# SCH___2021-11-10.net
KiCad netlist of a schematic drawn in EasyEDA
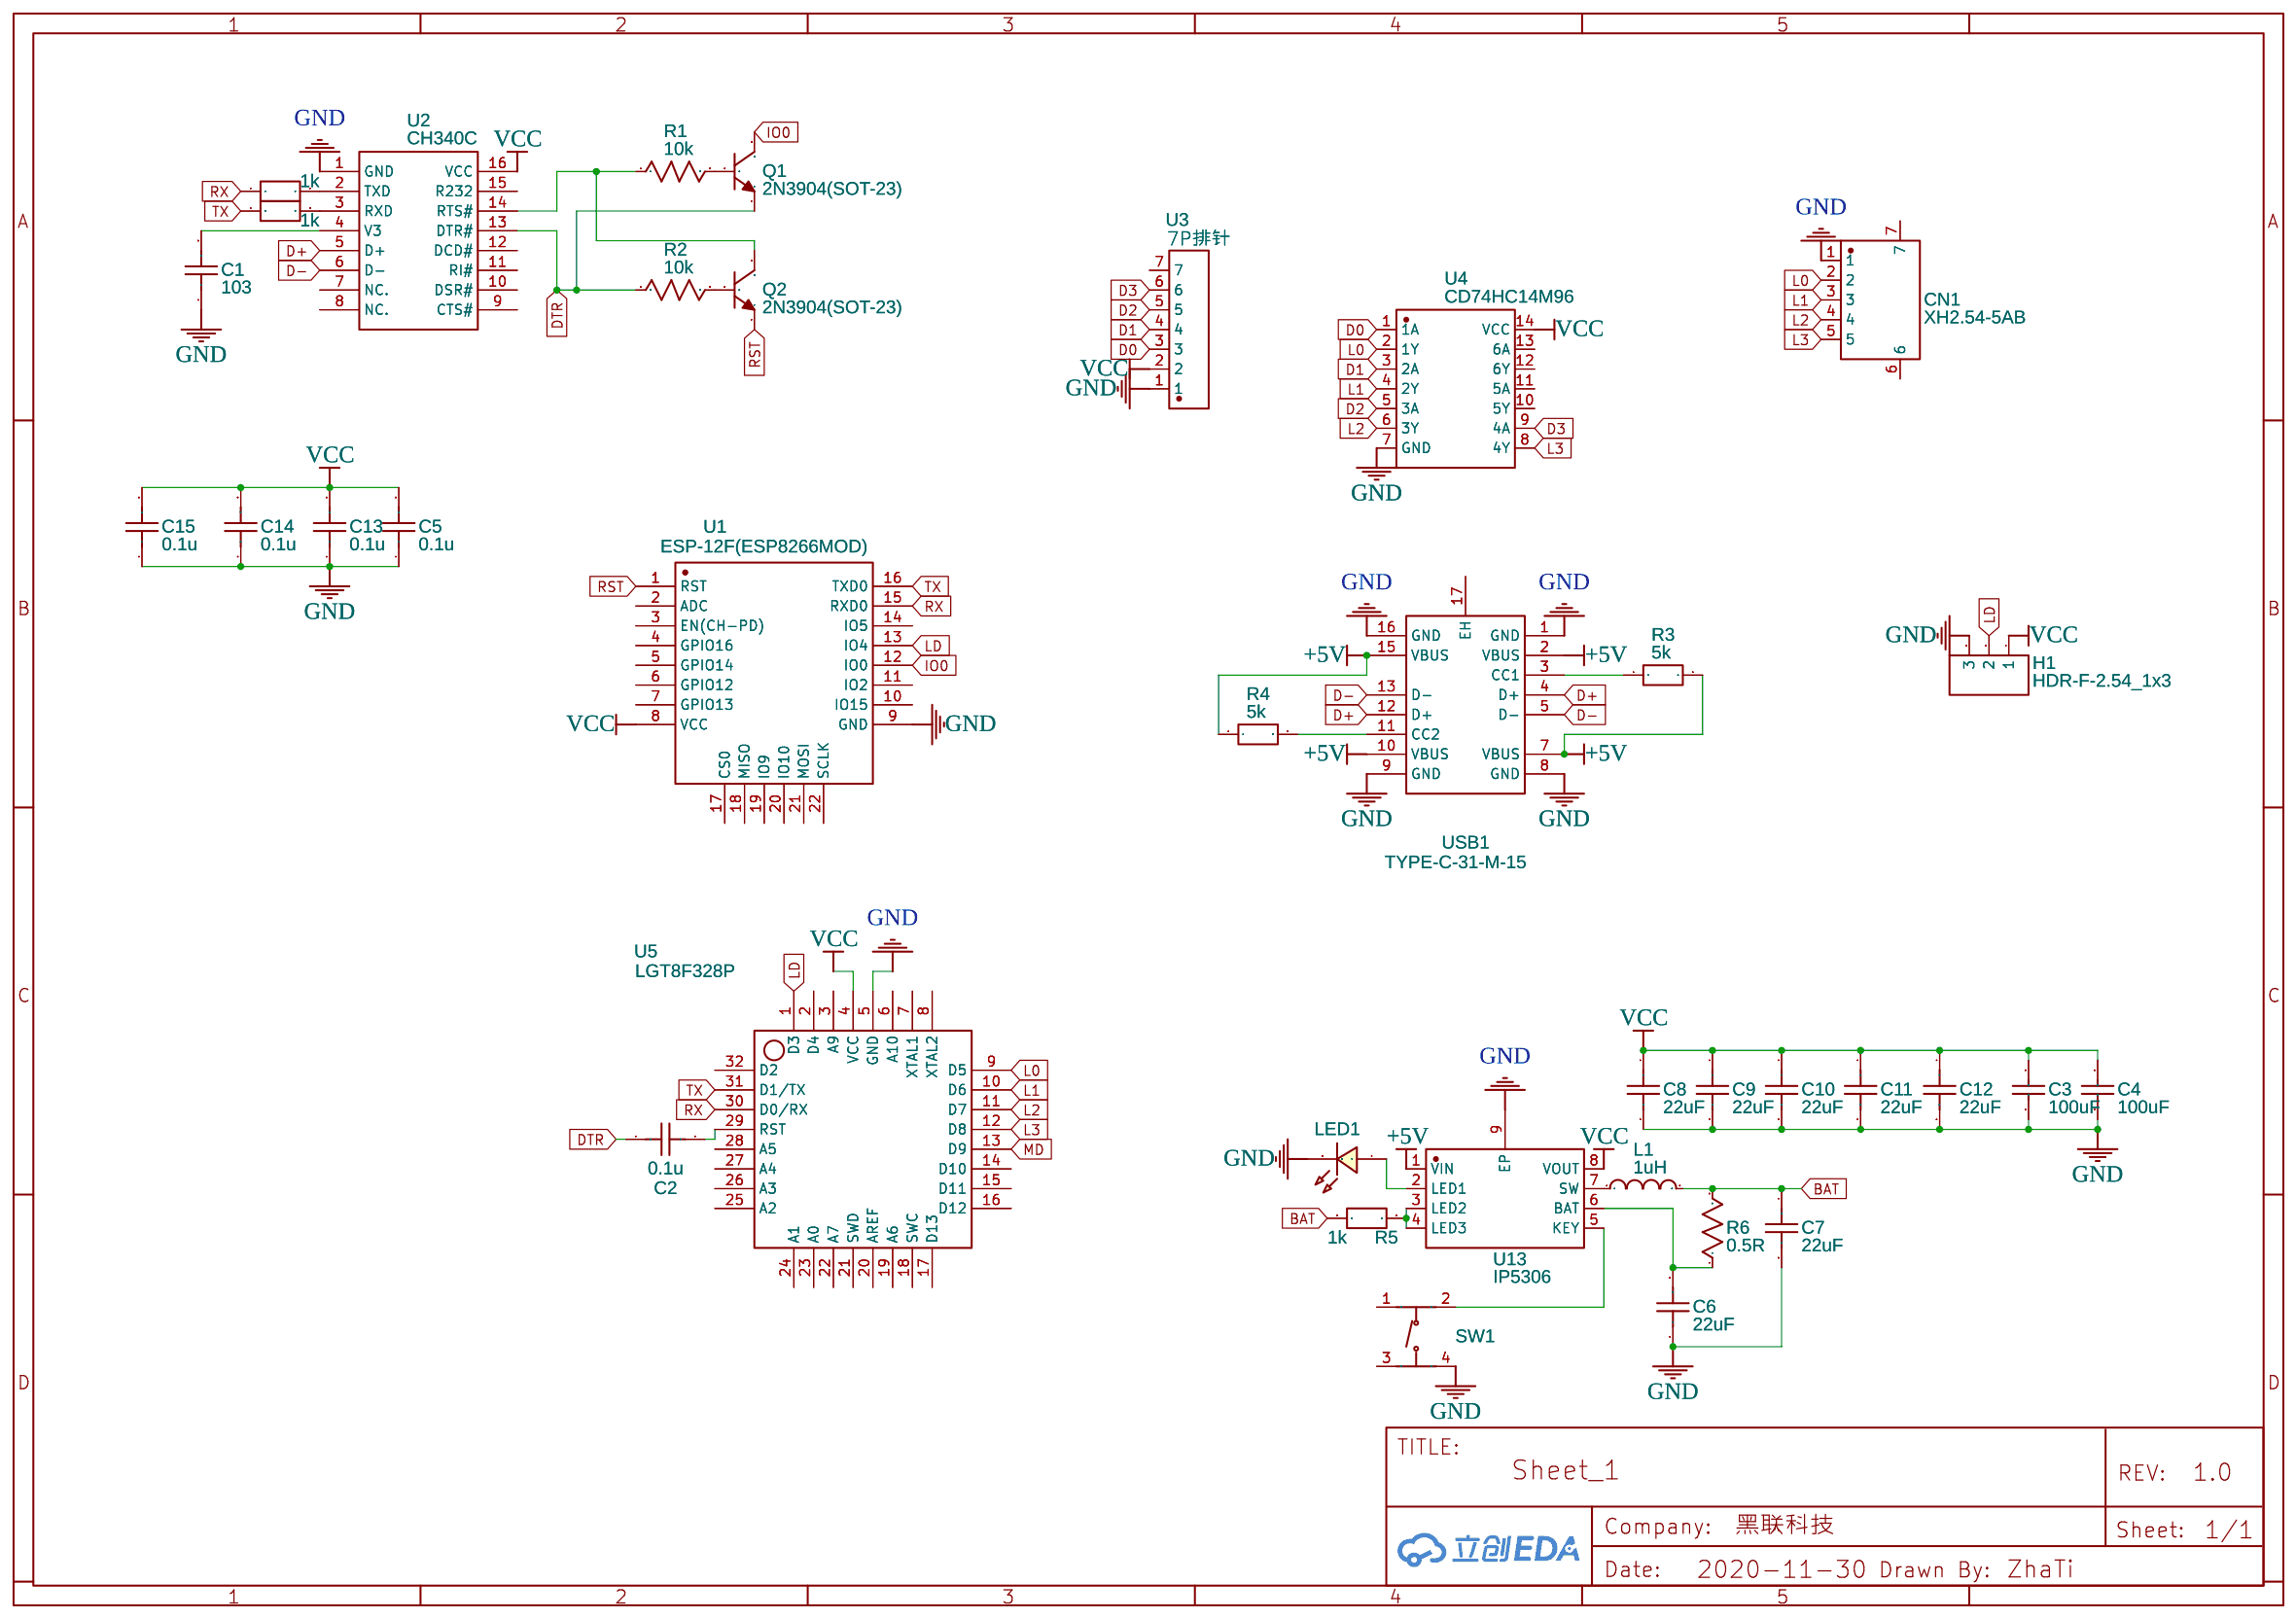
[diagram p0: schematic sheet]

(export (version "E")
  (design (tool "Eeschema 10.0.6"))
  (components
    (comp (ref "C1") (value "103") (libsource (lib "") (part "C_0603_US")))
    (comp (ref "C2") (value "0.1u") (libsource (lib "") (part "C_0603_US_1")))
    (comp (ref "C3")
      (value "100uF")
      (fields
        (field (name "BOM_Manufacturer Part") "1210B472K251NT")
        (field (name "BOM_Supplier Part") "C52019")
      )
      (libsource (lib "") (part "1210B472K251NT"))
    )
    (comp (ref "C4")
      (value "100uF")
      (fields
        (field (name "BOM_Manufacturer Part") "1210B472K251NT")
        (field (name "BOM_Supplier Part") "C52019")
      )
      (libsource (lib "") (part "1210B472K251NT"))
    )
    (comp (ref "C5") (value "0.1u") (libsource (lib "") (part "C_0603_US")))
    (comp (ref "C6")
      (value "22uF")
      (fields
        (field (name "BOM_Manufacturer Part") "CL21A226MQQNNNE")
        (field (name "BOM_Supplier Part") "C5674")
      )
      (libsource (lib "") (part "CL21A226MQQNNNE_1"))
    )
    (comp (ref "C7")
      (value "22uF")
      (fields
        (field (name "BOM_Manufacturer Part") "CL21A226MQQNNNE")
        (field (name "BOM_Supplier Part") "C5674")
      )
      (libsource (lib "") (part "CL21A226MQQNNNE"))
    )
    (comp (ref "C8")
      (value "22uF")
      (fields
        (field (name "BOM_Manufacturer Part") "CL21A226MQQNNNE")
        (field (name "BOM_Supplier Part") "C5674")
      )
      (libsource (lib "") (part "CL21A226MQQNNNE"))
    )
    (comp (ref "C9")
      (value "22uF")
      (fields
        (field (name "BOM_Manufacturer Part") "CL21A226MQQNNNE")
        (field (name "BOM_Supplier Part") "C5674")
      )
      (libsource (lib "") (part "CL21A226MQQNNNE"))
    )
    (comp (ref "C10")
      (value "22uF")
      (fields
        (field (name "BOM_Manufacturer Part") "CL21A226MQQNNNE")
        (field (name "BOM_Supplier Part") "C5674")
      )
      (libsource (lib "") (part "CL21A226MQQNNNE"))
    )
    (comp (ref "C11")
      (value "22uF")
      (fields
        (field (name "BOM_Manufacturer Part") "CL21A226MQQNNNE")
        (field (name "BOM_Supplier Part") "C5674")
      )
      (libsource (lib "") (part "CL21A226MQQNNNE"))
    )
    (comp (ref "C12")
      (value "22uF")
      (fields
        (field (name "BOM_Manufacturer Part") "CL21A226MQQNNNE")
        (field (name "BOM_Supplier Part") "C5674")
      )
      (libsource (lib "") (part "CL21A226MQQNNNE"))
    )
    (comp (ref "C13") (value "0.1u") (libsource (lib "") (part "C_0603_US")))
    (comp (ref "C14") (value "0.1u") (libsource (lib "") (part "C_0603_US")))
    (comp (ref "C15") (value "0.1u") (libsource (lib "") (part "C_0603_US")))
    (comp (ref "CN1")
      (value "XH2.54-5AB")
      (fields (field (name "BOM_Supplier Part") "C146128"))
      (libsource (lib "") (part "XH2.54-5AB"))
    )
    (comp (ref "H1")
      (value "HDR-F-2.54_1x3")
      (fields (field (name "BOM_Supplier Part") "C146690"))
      (libsource (lib "") (part "HDR-F-2.54_1x3"))
    )
    (comp (ref "L1")
      (value "1uH")
      (fields
        (field (name "BOM_Manufacturer Part") "SPM6530T-1R0M120")
        (field (name "BOM_Supplier Part") "C87572")
      )
      (libsource (lib "") (part "SPM6530T-1R0M120"))
    )
    (comp (ref "LED1")
      (value "LED-0603_R")
      (fields
        (field (name "BOM_Manufacturer Part") "19-217/R6C-AL1M2VY/3T")
        (field (name "BOM_Supplier Part") "C72044")
      )
      (libsource (lib "") (part "LED-0603_R"))
    )
    (comp (ref "Q1")
      (value "2N3904(SOT-23)")
      (fields
        (field (name "BOM_Manufacturer Part") "2n3904S-RTK/PS")
        (field (name "BOM_Supplier Part") "C18536")
      )
      (libsource (lib "") (part "2N3904(SOT-23)"))
    )
    (comp (ref "Q2")
      (value "2N3904(SOT-23)")
      (fields
        (field (name "BOM_Manufacturer Part") "2n3904S-RTK/PS")
        (field (name "BOM_Supplier Part") "C18536")
      )
      (libsource (lib "") (part "2N3904(SOT-23)"))
    )
    (comp (ref "R1") (value "10k") (libsource (lib "") (part "R_0603_US")))
    (comp (ref "R2") (value "10k") (libsource (lib "") (part "R_0603_US")))
    (comp (ref "R3") (value "5k") (libsource (lib "") (part "R_0603_EU")))
    (comp (ref "R4") (value "5k") (libsource (lib "") (part "R_0603_EU")))
    (comp (ref "R5") (value "1k") (libsource (lib "") (part "R_0603_EU")))
    (comp (ref "R6") (value "0.5R") (libsource (lib "") (part "R_0603_US_1")))
    (comp (ref "R7") (value "1k") (libsource (lib "") (part "R_0603_EU")))
    (comp (ref "R8") (value "1k") (libsource (lib "") (part "R_0603_EU")))
    (comp (ref "SW1")
      (value "TS-1187A-B-A-B")
      (fields (field (name "BOM_Supplier Part") "C318884"))
      (libsource (lib "") (part "TS-1187A-B-A-B"))
    )
    (comp (ref "U1")
      (value "ESP-12F(ESP8266MOD)")
      (fields (field (name "BOM_Supplier Part") "C82891"))
      (libsource (lib "") (part "ESP-12F(ESP8266MOD)"))
    )
    (comp (ref "U2")
      (value "CH340C")
      (fields (field (name "BOM_Supplier Part") "C84681"))
      (libsource (lib "") (part "CH340C"))
    )
    (comp (ref "U3") (value "7P排针") (libsource (lib "") (part "7P")))
    (comp (ref "U4")
      (value "CD74HC14M96")
      (fields (field (name "BOM_Supplier Part") "C74640"))
      (libsource (lib "") (part "CD74HC14M96"))
    )
    (comp (ref "U5") (value "LGT8F328P") (libsource (lib "") (part "LGT8F328P")))
    (comp (ref "U13")
      (value "IP5306")
      (fields (field (name "BOM_Supplier Part") "C181692"))
      (libsource (lib "") (part "IP5306"))
    )
    (comp (ref "USB1")
      (value "TYPE-C-31-M-15")
      (fields (field (name "BOM_Supplier Part") "C223908"))
      (libsource (lib "") (part "TYPE-C-31-M-15"))
    )
  )
  (nets
    (net (code "1") (name "+5V") (class "Default")
      (node (ref "R3") (pin "2") (pinfunction "2_2") (pintype "unspecified"))
      (node (ref "R4") (pin "1") (pinfunction "1_1") (pintype "unspecified"))
      (node (ref "U13") (pin "1") (pinfunction "VIN_1") (pintype "unspecified"))
      (node (ref "USB1") (pin "10") (pinfunction "VBUS_10") (pintype "unspecified"))
      (node (ref "USB1") (pin "15") (pinfunction "VBUS_15") (pintype "unspecified"))
      (node (ref "USB1") (pin "2") (pinfunction "VBUS_2") (pintype "unspecified"))
      (node (ref "USB1") (pin "7") (pinfunction "VBUS_7") (pintype "unspecified"))
    )
    (net (code "2") (name "BAT") (class "Default")
      (node (ref "C7") (pin "1") (pinfunction "1_1") (pintype "unspecified"))
      (node (ref "L1") (pin "2") (pinfunction "2_2") (pintype "unspecified"))
      (node (ref "R5") (pin "1") (pinfunction "1_1") (pintype "unspecified"))
      (node (ref "R6") (pin "2") (pinfunction "2_2") (pintype "unspecified"))
    )
    (net (code "3") (name "D+") (class "Default")
      (node (ref "U2") (pin "5") (pinfunction "D+_5") (pintype "unspecified"))
      (node (ref "USB1") (pin "12") (pinfunction "D+_12") (pintype "unspecified"))
      (node (ref "USB1") (pin "4") (pinfunction "D+_4") (pintype "unspecified"))
    )
    (net (code "4") (name "D-") (class "Default")
      (node (ref "U2") (pin "6") (pinfunction "D-_6") (pintype "unspecified"))
      (node (ref "USB1") (pin "13") (pinfunction "D-_13") (pintype "unspecified"))
      (node (ref "USB1") (pin "5") (pinfunction "D-_5") (pintype "unspecified"))
    )
    (net (code "5") (name "D0") (class "Default")
      (node (ref "U3") (pin "3") (pinfunction "3_3") (pintype "unspecified"))
      (node (ref "U4") (pin "1") (pinfunction "1A_1") (pintype "unspecified"))
    )
    (net (code "6") (name "D1") (class "Default")
      (node (ref "U3") (pin "4") (pinfunction "4_4") (pintype "unspecified"))
      (node (ref "U4") (pin "3") (pinfunction "2A_3") (pintype "unspecified"))
    )
    (net (code "7") (name "D2") (class "Default")
      (node (ref "U3") (pin "5") (pinfunction "5_5") (pintype "unspecified"))
      (node (ref "U4") (pin "5") (pinfunction "3A_5") (pintype "unspecified"))
    )
    (net (code "8") (name "D3") (class "Default")
      (node (ref "U3") (pin "6") (pinfunction "6_6") (pintype "unspecified"))
      (node (ref "U4") (pin "9") (pinfunction "4A_9") (pintype "unspecified"))
    )
    (net (code "9") (name "DTR") (class "Default")
      (node (ref "C2") (pin "1") (pinfunction "1_1") (pintype "unspecified"))
      (node (ref "Q1") (pin "1") (pinfunction "E_1") (pintype "input"))
      (node (ref "R2") (pin "1") (pinfunction "1_1") (pintype "unspecified"))
      (node (ref "U2") (pin "13") (pinfunction "DTR#_13") (pintype "unspecified"))
    )
    (net (code "10") (name "GND") (class "Default")
      (node (ref "C1") (pin "1") (pinfunction "1_1") (pintype "unspecified"))
      (node (ref "C10") (pin "2") (pinfunction "2_2") (pintype "unspecified"))
      (node (ref "C11") (pin "2") (pinfunction "2_2") (pintype "unspecified"))
      (node (ref "C12") (pin "2") (pinfunction "2_2") (pintype "unspecified"))
      (node (ref "C13") (pin "1") (pinfunction "1_1") (pintype "unspecified"))
      (node (ref "C14") (pin "1") (pinfunction "1_1") (pintype "unspecified"))
      (node (ref "C15") (pin "1") (pinfunction "1_1") (pintype "unspecified"))
      (node (ref "C3") (pin "1") (pinfunction "1_1") (pintype "input"))
      (node (ref "C4") (pin "1") (pinfunction "1_1") (pintype "input"))
      (node (ref "C5") (pin "1") (pinfunction "1_1") (pintype "unspecified"))
      (node (ref "C6") (pin "1") (pinfunction "1_1") (pintype "unspecified"))
      (node (ref "C7") (pin "2") (pinfunction "2_2") (pintype "unspecified"))
      (node (ref "C8") (pin "2") (pinfunction "2_2") (pintype "unspecified"))
      (node (ref "C9") (pin "2") (pinfunction "2_2") (pintype "unspecified"))
      (node (ref "CN1") (pin "1") (pinfunction "1_1") (pintype "unspecified"))
      (node (ref "H1") (pin "3") (pinfunction "3_3") (pintype "input"))
      (node (ref "LED1") (pin "2") (pinfunction "2_2") (pintype "unspecified"))
      (node (ref "SW1") (pin "4") (pinfunction "D_4") (pintype "unspecified"))
      (node (ref "U1") (pin "9") (pinfunction "GND_9") (pintype "unspecified"))
      (node (ref "U13") (pin "9") (pinfunction "EP_9") (pintype "unspecified"))
      (node (ref "U2") (pin "1") (pinfunction "GND_1") (pintype "unspecified"))
      (node (ref "U3") (pin "1") (pinfunction "1_1") (pintype "unspecified"))
      (node (ref "U4") (pin "7") (pinfunction "GND_7") (pintype "unspecified"))
      (node (ref "U5") (pin "5") (pinfunction "GND_5") (pintype "unspecified"))
      (node (ref "USB1") (pin "1") (pinfunction "GND_1") (pintype "unspecified"))
      (node (ref "USB1") (pin "16") (pinfunction "GND_16") (pintype "unspecified"))
      (node (ref "USB1") (pin "8") (pinfunction "GND_8") (pintype "unspecified"))
      (node (ref "USB1") (pin "9") (pinfunction "GND_9") (pintype "unspecified"))
    )
    (net (code "11") (name "IO0") (class "Default")
      (node (ref "Q1") (pin "3") (pinfunction "C_3") (pintype "input"))
      (node (ref "U1") (pin "12") (pinfunction "IO0_12") (pintype "unspecified"))
    )
    (net (code "12") (name "L0") (class "Default")
      (node (ref "CN1") (pin "2") (pinfunction "2_2") (pintype "unspecified"))
      (node (ref "U4") (pin "2") (pinfunction "1Y_2") (pintype "unspecified"))
      (node (ref "U5") (pin "9") (pinfunction "D5_9") (pintype "unspecified"))
    )
    (net (code "13") (name "L1") (class "Default")
      (node (ref "CN1") (pin "3") (pinfunction "3_3") (pintype "unspecified"))
      (node (ref "U4") (pin "4") (pinfunction "2Y_4") (pintype "unspecified"))
      (node (ref "U5") (pin "10") (pinfunction "D6_10") (pintype "unspecified"))
    )
    (net (code "14") (name "L2") (class "Default")
      (node (ref "CN1") (pin "4") (pinfunction "4_4") (pintype "unspecified"))
      (node (ref "U4") (pin "6") (pinfunction "3Y_6") (pintype "unspecified"))
      (node (ref "U5") (pin "11") (pinfunction "D7_11") (pintype "unspecified"))
    )
    (net (code "15") (name "L3") (class "Default")
      (node (ref "CN1") (pin "5") (pinfunction "5_5") (pintype "unspecified"))
      (node (ref "U4") (pin "8") (pinfunction "4Y_8") (pintype "unspecified"))
      (node (ref "U5") (pin "12") (pinfunction "D8_12") (pintype "unspecified"))
    )
    (net (code "16") (name "LD") (class "Default")
      (node (ref "H1") (pin "2") (pinfunction "2_2") (pintype "input"))
      (node (ref "U1") (pin "13") (pinfunction "IO4_13") (pintype "unspecified"))
      (node (ref "U5") (pin "1") (pinfunction "D3_1") (pintype "unspecified"))
    )
    (net (code "17") (name "MD") (class "Default")
      (node (ref "U5") (pin "13") (pinfunction "D9_13") (pintype "unspecified"))
    )
    (net (code "18") (name "Net-(Q1-B)") (class "Default")
      (node (ref "Q1") (pin "2") (pinfunction "B_2") (pintype "input"))
      (node (ref "R1") (pin "2") (pinfunction "2_2") (pintype "unspecified"))
    )
    (net (code "19") (name "Net-(Q2-B)") (class "Default")
      (node (ref "Q2") (pin "2") (pinfunction "B_2") (pintype "input"))
      (node (ref "R2") (pin "2") (pinfunction "2_2") (pintype "unspecified"))
    )
    (net (code "20") (name "Net-(Q2-C)") (class "Default")
      (node (ref "Q2") (pin "3") (pinfunction "C_3") (pintype "input"))
      (node (ref "R1") (pin "1") (pinfunction "1_1") (pintype "unspecified"))
      (node (ref "U2") (pin "14") (pinfunction "RTS#_14") (pintype "unspecified"))
    )
    (net (code "21") (name "Net-(SW1-B)") (class "Default")
      (node (ref "SW1") (pin "2") (pinfunction "B_2") (pintype "unspecified"))
      (node (ref "U13") (pin "5") (pinfunction "KEY_5") (pintype "unspecified"))
    )
    (net (code "22") (name "Net-(U2-RXD)") (class "Default")
      (node (ref "R8") (pin "2") (pinfunction "2_2") (pintype "unspecified"))
      (node (ref "U2") (pin "3") (pinfunction "RXD_3") (pintype "unspecified"))
    )
    (net (code "23") (name "Net-(U2-TXD)") (class "Default")
      (node (ref "R7") (pin "2") (pinfunction "2_2") (pintype "unspecified"))
      (node (ref "U2") (pin "2") (pinfunction "TXD_2") (pintype "unspecified"))
    )
    (net (code "24") (name "Net-(U2-V3)") (class "Default")
      (node (ref "C1") (pin "2") (pinfunction "2_2") (pintype "unspecified"))
      (node (ref "U2") (pin "4") (pinfunction "V3_4") (pintype "unspecified"))
    )
    (net (code "25") (name "Net-(U5-RST)") (class "Default")
      (node (ref "C2") (pin "2") (pinfunction "2_2") (pintype "unspecified"))
      (node (ref "U5") (pin "29") (pinfunction "RST_29") (pintype "unspecified"))
    )
    (net (code "26") (name "Net-(U13-BAT)") (class "Default")
      (node (ref "C6") (pin "2") (pinfunction "2_2") (pintype "unspecified"))
      (node (ref "R6") (pin "1") (pinfunction "1_1") (pintype "unspecified"))
      (node (ref "U13") (pin "6") (pinfunction "BAT_6") (pintype "unspecified"))
    )
    (net (code "27") (name "Net-(U13-LED1)") (class "Default")
      (node (ref "LED1") (pin "1") (pinfunction "1_1") (pintype "unspecified"))
      (node (ref "U13") (pin "2") (pinfunction "LED1_2") (pintype "unspecified"))
    )
    (net (code "28") (name "Net-(U13-LED2)") (class "Default")
      (node (ref "R5") (pin "2") (pinfunction "2_2") (pintype "unspecified"))
      (node (ref "U13") (pin "3") (pinfunction "LED2_3") (pintype "unspecified"))
      (node (ref "U13") (pin "4") (pinfunction "LED3_4") (pintype "unspecified"))
    )
    (net (code "29") (name "Net-(U13-SW)") (class "Default")
      (node (ref "L1") (pin "1") (pinfunction "1_1") (pintype "unspecified"))
      (node (ref "U13") (pin "7") (pinfunction "SW_7") (pintype "unspecified"))
    )
    (net (code "30") (name "Net-(USB1-CC1)") (class "Default")
      (node (ref "R3") (pin "1") (pinfunction "1_1") (pintype "unspecified"))
      (node (ref "USB1") (pin "3") (pinfunction "CC1_3") (pintype "unspecified"))
    )
    (net (code "31") (name "Net-(USB1-CC2)") (class "Default")
      (node (ref "R4") (pin "2") (pinfunction "2_2") (pintype "unspecified"))
      (node (ref "USB1") (pin "11") (pinfunction "CC2_11") (pintype "unspecified"))
    )
    (net (code "32") (name "RST") (class "Default")
      (node (ref "Q2") (pin "1") (pinfunction "E_1") (pintype "input"))
      (node (ref "U1") (pin "1") (pinfunction "RST_1") (pintype "unspecified"))
    )
    (net (code "33") (name "RX") (class "Default")
      (node (ref "R7") (pin "1") (pinfunction "1_1") (pintype "unspecified"))
      (node (ref "U1") (pin "15") (pinfunction "RXD0_15") (pintype "unspecified"))
      (node (ref "U5") (pin "30") (pinfunction "D0/RX_30") (pintype "unspecified"))
    )
    (net (code "34") (name "TX") (class "Default")
      (node (ref "R8") (pin "1") (pinfunction "1_1") (pintype "unspecified"))
      (node (ref "U1") (pin "16") (pinfunction "TXD0_16") (pintype "unspecified"))
      (node (ref "U5") (pin "31") (pinfunction "D1/TX_31") (pintype "unspecified"))
    )
    (net (code "35") (name "VCC") (class "Default")
      (node (ref "C10") (pin "1") (pinfunction "1_1") (pintype "unspecified"))
      (node (ref "C11") (pin "1") (pinfunction "1_1") (pintype "unspecified"))
      (node (ref "C12") (pin "1") (pinfunction "1_1") (pintype "unspecified"))
      (node (ref "C13") (pin "2") (pinfunction "2_2") (pintype "unspecified"))
      (node (ref "C14") (pin "2") (pinfunction "2_2") (pintype "unspecified"))
      (node (ref "C15") (pin "2") (pinfunction "2_2") (pintype "unspecified"))
      (node (ref "C3") (pin "2") (pinfunction "2_2") (pintype "input"))
      (node (ref "C4") (pin "2") (pinfunction "2_2") (pintype "input"))
      (node (ref "C5") (pin "2") (pinfunction "2_2") (pintype "unspecified"))
      (node (ref "C8") (pin "1") (pinfunction "1_1") (pintype "unspecified"))
      (node (ref "C9") (pin "1") (pinfunction "1_1") (pintype "unspecified"))
      (node (ref "H1") (pin "1") (pinfunction "1_1") (pintype "input"))
      (node (ref "U1") (pin "8") (pinfunction "VCC_8") (pintype "unspecified"))
      (node (ref "U13") (pin "8") (pinfunction "VOUT_8") (pintype "unspecified"))
      (node (ref "U2") (pin "16") (pinfunction "VCC_16") (pintype "unspecified"))
      (node (ref "U3") (pin "2") (pinfunction "2_2") (pintype "unspecified"))
      (node (ref "U4") (pin "14") (pinfunction "VCC_14") (pintype "unspecified"))
      (node (ref "U5") (pin "4") (pinfunction "VCC_4") (pintype "unspecified"))
    )
    (net (code "36") (name "unconnected-(CN1-Pad6)") (class "Default")
      (node (ref "CN1") (pin "6") (pinfunction "6_6") (pintype "unspecified"))
    )
    (net (code "37") (name "unconnected-(CN1-Pad7)") (class "Default")
      (node (ref "CN1") (pin "7") (pinfunction "7_7") (pintype "unspecified"))
    )
    (net (code "38") (name "unconnected-(SW1-A-Pad1)") (class "Default")
      (node (ref "SW1") (pin "1") (pinfunction "A_1") (pintype "unspecified"))
    )
    (net (code "39") (name "unconnected-(SW1-C-Pad3)") (class "Default")
      (node (ref "SW1") (pin "3") (pinfunction "C_3") (pintype "unspecified"))
    )
    (net (code "40") (name "unconnected-(U1-ADC-Pad2)") (class "Default")
      (node (ref "U1") (pin "2") (pinfunction "ADC_2") (pintype "unspecified"))
    )
    (net (code "41") (name "unconnected-(U1-CS0-Pad17)") (class "Default")
      (node (ref "U1") (pin "17") (pinfunction "CS0_17") (pintype "unspecified"))
    )
    (net (code "42") (name "unconnected-(U1-EN(CH-PD)-Pad3)") (class "Default")
      (node (ref "U1") (pin "3") (pinfunction "EN(CH-PD)_3") (pintype "unspecified"))
    )
    (net (code "43") (name "unconnected-(U1-GPIO12-Pad6)") (class "Default")
      (node (ref "U1") (pin "6") (pinfunction "GPIO12_6") (pintype "unspecified"))
    )
    (net (code "44") (name "unconnected-(U1-GPIO13-Pad7)") (class "Default")
      (node (ref "U1") (pin "7") (pinfunction "GPIO13_7") (pintype "unspecified"))
    )
    (net (code "45") (name "unconnected-(U1-GPIO14-Pad5)") (class "Default")
      (node (ref "U1") (pin "5") (pinfunction "GPIO14_5") (pintype "unspecified"))
    )
    (net (code "46") (name "unconnected-(U1-GPIO16-Pad4)") (class "Default")
      (node (ref "U1") (pin "4") (pinfunction "GPIO16_4") (pintype "unspecified"))
    )
    (net (code "47") (name "unconnected-(U1-IO2-Pad11)") (class "Default")
      (node (ref "U1") (pin "11") (pinfunction "IO2_11") (pintype "unspecified"))
    )
    (net (code "48") (name "unconnected-(U1-IO5-Pad14)") (class "Default")
      (node (ref "U1") (pin "14") (pinfunction "IO5_14") (pintype "unspecified"))
    )
    (net (code "49") (name "unconnected-(U1-IO9-Pad19)") (class "Default")
      (node (ref "U1") (pin "19") (pinfunction "IO9_19") (pintype "unspecified"))
    )
    (net (code "50") (name "unconnected-(U1-IO10-Pad20)") (class "Default")
      (node (ref "U1") (pin "20") (pinfunction "IO10_20") (pintype "unspecified"))
    )
    (net (code "51") (name "unconnected-(U1-IO15-Pad10)") (class "Default")
      (node (ref "U1") (pin "10") (pinfunction "IO15_10") (pintype "unspecified"))
    )
    (net (code "52") (name "unconnected-(U1-MISO-Pad18)") (class "Default")
      (node (ref "U1") (pin "18") (pinfunction "MISO_18") (pintype "unspecified"))
    )
    (net (code "53") (name "unconnected-(U1-MOSI-Pad21)") (class "Default")
      (node (ref "U1") (pin "21") (pinfunction "MOSI_21") (pintype "unspecified"))
    )
    (net (code "54") (name "unconnected-(U1-SCLK-Pad22)") (class "Default")
      (node (ref "U1") (pin "22") (pinfunction "SCLK_22") (pintype "unspecified"))
    )
    (net (code "55") (name "unconnected-(U2-CTS#-Pad9)") (class "Default")
      (node (ref "U2") (pin "9") (pinfunction "CTS#_9") (pintype "unspecified"))
    )
    (net (code "56") (name "unconnected-(U2-DCD#-Pad12)") (class "Default")
      (node (ref "U2") (pin "12") (pinfunction "DCD#_12") (pintype "unspecified"))
    )
    (net (code "57") (name "unconnected-(U2-DSR#-Pad10)") (class "Default")
      (node (ref "U2") (pin "10") (pinfunction "DSR#_10") (pintype "unspecified"))
    )
    (net (code "58") (name "unconnected-(U2-NC.-Pad7)") (class "Default")
      (node (ref "U2") (pin "7") (pinfunction "NC._7") (pintype "unspecified"))
    )
    (net (code "59") (name "unconnected-(U2-NC.-Pad8)") (class "Default")
      (node (ref "U2") (pin "8") (pinfunction "NC._8") (pintype "unspecified"))
    )
    (net (code "60") (name "unconnected-(U2-R232-Pad15)") (class "Default")
      (node (ref "U2") (pin "15") (pinfunction "R232_15") (pintype "unspecified"))
    )
    (net (code "61") (name "unconnected-(U2-RI#-Pad11)") (class "Default")
      (node (ref "U2") (pin "11") (pinfunction "RI#_11") (pintype "unspecified"))
    )
    (net (code "62") (name "unconnected-(U3-Pad7)") (class "Default")
      (node (ref "U3") (pin "7") (pinfunction "7_7") (pintype "unspecified"))
    )
    (net (code "63") (name "unconnected-(U4-5A-Pad11)") (class "Default")
      (node (ref "U4") (pin "11") (pinfunction "5A_11") (pintype "unspecified"))
    )
    (net (code "64") (name "unconnected-(U4-5Y-Pad10)") (class "Default")
      (node (ref "U4") (pin "10") (pinfunction "5Y_10") (pintype "unspecified"))
    )
    (net (code "65") (name "unconnected-(U4-6A-Pad13)") (class "Default")
      (node (ref "U4") (pin "13") (pinfunction "6A_13") (pintype "unspecified"))
    )
    (net (code "66") (name "unconnected-(U4-6Y-Pad12)") (class "Default")
      (node (ref "U4") (pin "12") (pinfunction "6Y_12") (pintype "unspecified"))
    )
    (net (code "67") (name "unconnected-(U5-A0-Pad23)") (class "Default")
      (node (ref "U5") (pin "23") (pinfunction "A0_23") (pintype "unspecified"))
    )
    (net (code "68") (name "unconnected-(U5-A1-Pad24)") (class "Default")
      (node (ref "U5") (pin "24") (pinfunction "A1_24") (pintype "unspecified"))
    )
    (net (code "69") (name "unconnected-(U5-A2-Pad25)") (class "Default")
      (node (ref "U5") (pin "25") (pinfunction "A2_25") (pintype "unspecified"))
    )
    (net (code "70") (name "unconnected-(U5-A3-Pad26)") (class "Default")
      (node (ref "U5") (pin "26") (pinfunction "A3_26") (pintype "unspecified"))
    )
    (net (code "71") (name "unconnected-(U5-A4-Pad27)") (class "Default")
      (node (ref "U5") (pin "27") (pinfunction "A4_27") (pintype "unspecified"))
    )
    (net (code "72") (name "unconnected-(U5-A5-Pad28)") (class "Default")
      (node (ref "U5") (pin "28") (pinfunction "A5_28") (pintype "unspecified"))
    )
    (net (code "73") (name "unconnected-(U5-A6-Pad19)") (class "Default")
      (node (ref "U5") (pin "19") (pinfunction "A6_19") (pintype "unspecified"))
    )
    (net (code "74") (name "unconnected-(U5-A7-Pad22)") (class "Default")
      (node (ref "U5") (pin "22") (pinfunction "A7_22") (pintype "unspecified"))
    )
    (net (code "75") (name "unconnected-(U5-A9-Pad3)") (class "Default")
      (node (ref "U5") (pin "3") (pinfunction "A9_3") (pintype "unspecified"))
    )
    (net (code "76") (name "unconnected-(U5-A10-Pad6)") (class "Default")
      (node (ref "U5") (pin "6") (pinfunction "A10_6") (pintype "unspecified"))
    )
    (net (code "77") (name "unconnected-(U5-AREF-Pad20)") (class "Default")
      (node (ref "U5") (pin "20") (pinfunction "AREF_20") (pintype "unspecified"))
    )
    (net (code "78") (name "unconnected-(U5-D2-Pad32)") (class "Default")
      (node (ref "U5") (pin "32") (pinfunction "D2_32") (pintype "unspecified"))
    )
    (net (code "79") (name "unconnected-(U5-D4-Pad2)") (class "Default")
      (node (ref "U5") (pin "2") (pinfunction "D4_2") (pintype "unspecified"))
    )
    (net (code "80") (name "unconnected-(U5-D10-Pad14)") (class "Default")
      (node (ref "U5") (pin "14") (pinfunction "D10_14") (pintype "unspecified"))
    )
    (net (code "81") (name "unconnected-(U5-D11-Pad15)") (class "Default")
      (node (ref "U5") (pin "15") (pinfunction "D11_15") (pintype "unspecified"))
    )
    (net (code "82") (name "unconnected-(U5-D12-Pad16)") (class "Default")
      (node (ref "U5") (pin "16") (pinfunction "D12_16") (pintype "unspecified"))
    )
    (net (code "83") (name "unconnected-(U5-D13-Pad17)") (class "Default")
      (node (ref "U5") (pin "17") (pinfunction "D13_17") (pintype "unspecified"))
    )
    (net (code "84") (name "unconnected-(U5-SWC-Pad18)") (class "Default")
      (node (ref "U5") (pin "18") (pinfunction "SWC_18") (pintype "unspecified"))
    )
    (net (code "85") (name "unconnected-(U5-SWD-Pad21)") (class "Default")
      (node (ref "U5") (pin "21") (pinfunction "SWD_21") (pintype "unspecified"))
    )
    (net (code "86") (name "unconnected-(U5-XTAL1-Pad7)") (class "Default")
      (node (ref "U5") (pin "7") (pinfunction "XTAL1_7") (pintype "unspecified"))
    )
    (net (code "87") (name "unconnected-(U5-XTAL2-Pad8)") (class "Default")
      (node (ref "U5") (pin "8") (pinfunction "XTAL2_8") (pintype "unspecified"))
    )
    (net (code "88") (name "unconnected-(USB1-EH-Pad17)") (class "Default")
      (node (ref "USB1") (pin "17") (pinfunction "EH_17") (pintype "unspecified"))
    )
  )
)
